# PowerStage.net
KiCad netlist of a schematic drawn in Altium Designer
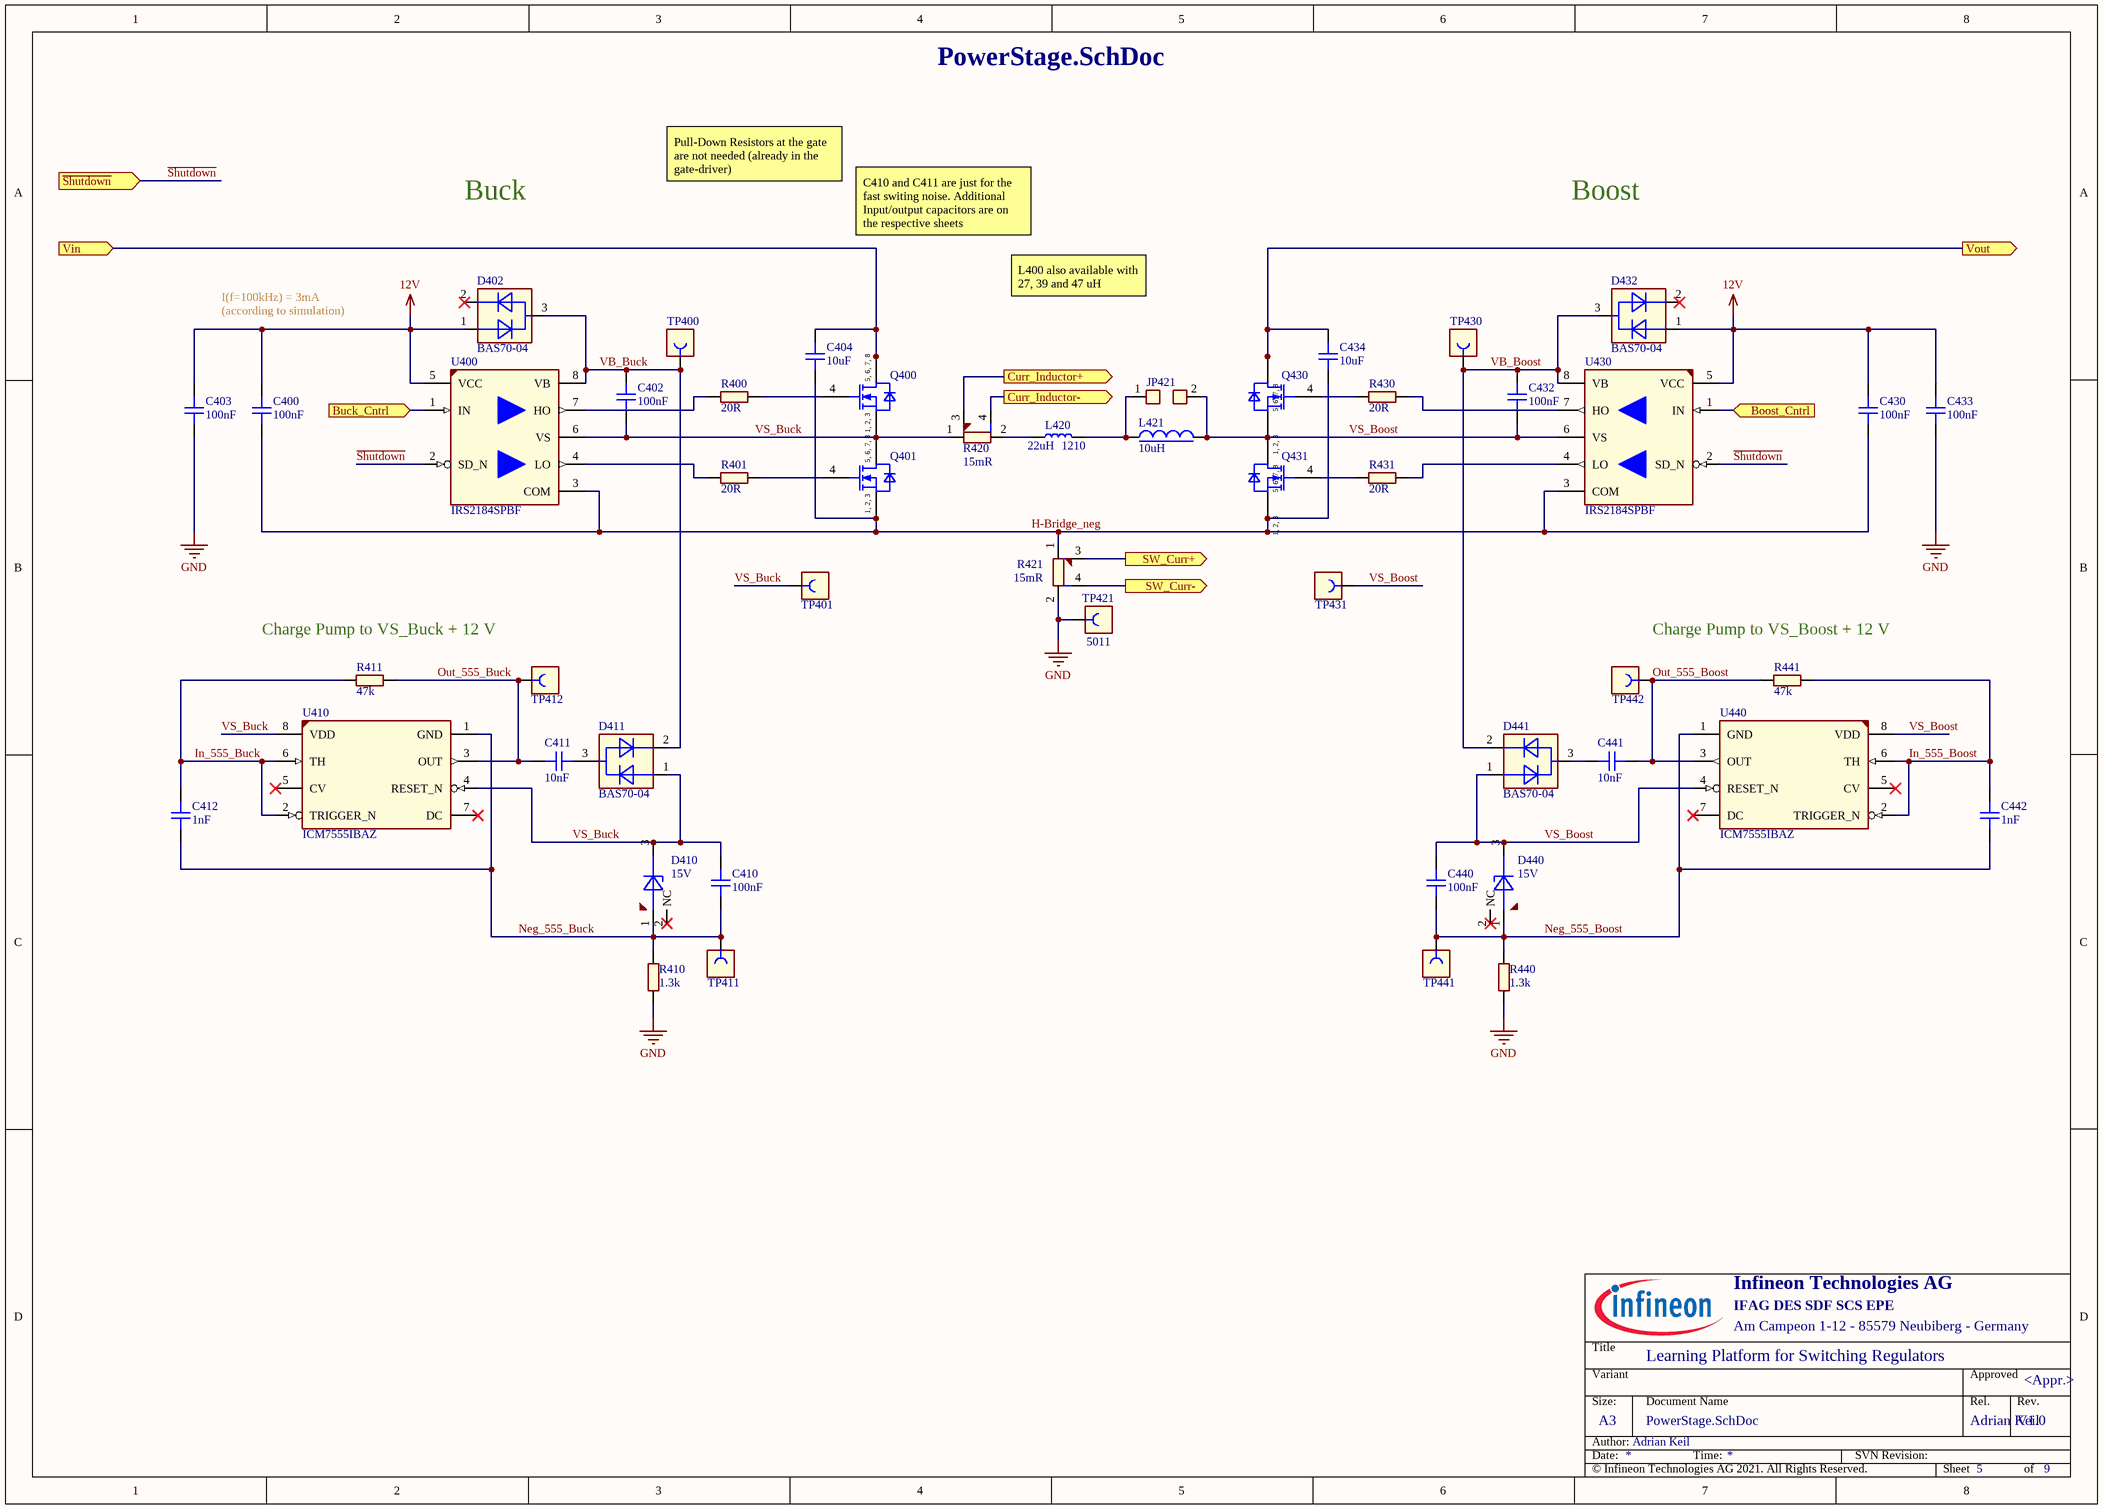
[diagram p0: PowerStage.SchDoc]

(export (version "E")
  (design (tool "Eeschema 10.0.6"))
  (components
    (comp (ref "C400")
      (value "100nF")
      (footprint "CAPC1608X90N-2")
      (description "CAP / CERA / 100nF / 50V / 10% / X7R (EIA) / -55°C to 125°C / 0603 / SMD / -")
      (fields (field (name "MANUFACTURER") "AVX"))
      (libsource (lib "PCBLibraryData") (part "CAP-SGL-STD-02P_00000001"))
    )
    (comp (ref "C402")
      (value "100nF")
      (footprint "CAPC1608X90N-2")
      (description "CAP / CERA / 100nF / 50V / 10% / X7R (EIA) / -55°C to 125°C / 0603 / SMD / -")
      (fields (field (name "MANUFACTURER") "AVX"))
      (libsource (lib "PCBLibraryData") (part "CAP-SGL-STD-02P_00000001"))
    )
    (comp (ref "C403")
      (value "100nF")
      (footprint "CAPC1608X90N-2")
      (description "CAP / CERA / 100nF / 50V / 10% / X7R (EIA) / -55°C to 125°C / 0603 / SMD / -")
      (fields (field (name "MANUFACTURER") "AVX"))
      (libsource (lib "PCBLibraryData") (part "CAP-SGL-STD-02P_00000001"))
    )
    (comp (ref "C404")
      (value "10uF")
      (footprint "CAPC3216X190N-1")
      (description "CAP / CERA / 10uF / 50V / 20% / X5R (EIA) / -55°C to 85°C / 1206 (3216) / SMD / -")
      (fields (field (name "MANUFACTURER") "Taiyo Yuden"))
      (libsource (lib "PCBLibraryData") (part "CAP-SGL-STD-02P_00000001"))
    )
    (comp (ref "C410")
      (value "100nF")
      (footprint "CAPC1608X90N-2")
      (description "CAP / CERA / 100nF / 50V / 10% / X7R (EIA) / -55°C to 125°C / 0603 / SMD / -")
      (fields (field (name "MANUFACTURER") "AVX"))
      (libsource (lib "PCBLibraryData") (part "CAP-SGL-STD-02P_00000001"))
    )
    (comp (ref "C411")
      (value "10nF")
      (footprint "CAPC1608X90N-4")
      (description "CAP / CERA / 10nF / 50V / 10% / X8R (EIA) / -55°C to 150°C / 0603(1608) / SMD / -")
      (fields
        (field (name "LEGACY PARTNUMBER") "CAP01010834")
        (field (name "MANUFACTURER") "TDK Corporation")
      )
      (libsource (lib "PCBLibraryData") (part "CAP-SGL-STD-02P_00000001"))
    )
    (comp (ref "C412")
      (value "1nF")
      (footprint "CAPC1608X87N-1")
      (description "CAP / CERA / 1nF / 50V / 10% / X7R (EIA) / -55°C to 125°C / 0603 (1608) / SMD / -")
      (fields (field (name "MANUFACTURER") "Wurth Elektronik"))
      (libsource (lib "PCBLibraryData") (part "CAP-SGL-STD-02P_00000001"))
    )
    (comp (ref "C430")
      (value "100nF")
      (footprint "CAPC1608X90N-2")
      (description "CAP / CERA / 100nF / 50V / 10% / X7R (EIA) / -55°C to 125°C / 0603 / SMD / -")
      (fields (field (name "MANUFACTURER") "AVX"))
      (libsource (lib "PCBLibraryData") (part "CAP-SGL-STD-02P_00000001"))
    )
    (comp (ref "C432")
      (value "100nF")
      (footprint "CAPC1608X90N-2")
      (description "CAP / CERA / 100nF / 50V / 10% / X7R (EIA) / -55°C to 125°C / 0603 / SMD / -")
      (fields (field (name "MANUFACTURER") "AVX"))
      (libsource (lib "PCBLibraryData") (part "CAP-SGL-STD-02P_00000001"))
    )
    (comp (ref "C433")
      (value "100nF")
      (footprint "CAPC1608X90N-2")
      (description "CAP / CERA / 100nF / 50V / 10% / X7R (EIA) / -55°C to 125°C / 0603 / SMD / -")
      (fields (field (name "MANUFACTURER") "AVX"))
      (libsource (lib "PCBLibraryData") (part "CAP-SGL-STD-02P_00000001"))
    )
    (comp (ref "C434")
      (value "10uF")
      (footprint "CAPC3216X190N-1")
      (description "CAP / CERA / 10uF / 50V / 20% / X5R (EIA) / -55°C to 85°C / 1206 (3216) / SMD / -")
      (fields (field (name "MANUFACTURER") "Taiyo Yuden"))
      (libsource (lib "PCBLibraryData") (part "CAP-SGL-STD-02P_00000001"))
    )
    (comp (ref "C440")
      (value "100nF")
      (footprint "CAPC1608X90N-2")
      (description "CAP / CERA / 100nF / 50V / 10% / X7R (EIA) / -55°C to 125°C / 0603 / SMD / -")
      (fields (field (name "MANUFACTURER") "AVX"))
      (libsource (lib "PCBLibraryData") (part "CAP-SGL-STD-02P_00000001"))
    )
    (comp (ref "C441")
      (value "10nF")
      (footprint "CAPC1608X90N-4")
      (description "CAP / CERA / 10nF / 50V / 10% / X8R (EIA) / -55°C to 150°C / 0603(1608) / SMD / -")
      (fields
        (field (name "LEGACY PARTNUMBER") "CAP01010834")
        (field (name "MANUFACTURER") "TDK Corporation")
      )
      (libsource (lib "PCBLibraryData") (part "CAP-SGL-STD-02P_00000001"))
    )
    (comp (ref "C442")
      (value "1nF")
      (footprint "CAPC1608X87N-1")
      (description "CAP / CERA / 1nF / 50V / 10% / X7R (EIA) / -55°C to 125°C / 0603 (1608) / SMD / -")
      (fields (field (name "MANUFACTURER") "Wurth Elektronik"))
      (libsource (lib "PCBLibraryData") (part "CAP-SGL-STD-02P_00000001"))
    )
    (comp (ref "D402")
      (value "BAS70-04")
      (footprint "SOT95P240X110-3N-1")
      (description "Silicon Schottky Diode")
      (fields
        (field (name "LEGACY PARTNUMBER") "IFX01400573")
        (field (name "MANUFACTURER") "Infineon Technologies")
      )
      (libsource (lib "") (part "d_dual_a1c2ac3_3p_1"))
    )
    (comp (ref "D410")
      (value "15V")
      (footprint "SOT95P237X111-3N-1")
      (fields (field (name "MANUFACTURER") "ON Semiconductor"))
      (libsource (lib "PCBLibraryData") (part "d_zener_a1c3_3p"))
    )
    (comp (ref "D411")
      (value "BAS70-04")
      (footprint "SOT95P240X110-3N-1")
      (description "Silicon Schottky Diode")
      (fields
        (field (name "LEGACY PARTNUMBER") "IFX01400573")
        (field (name "MANUFACTURER") "Infineon Technologies")
      )
      (libsource (lib "PCBLibraryData") (part "d_dual_a1c2ac3_3p"))
    )
    (comp (ref "D432")
      (value "BAS70-04")
      (footprint "SOT95P240X110-3N-1")
      (description "Silicon Schottky Diode")
      (fields
        (field (name "LEGACY PARTNUMBER") "IFX01400573")
        (field (name "MANUFACTURER") "Infineon Technologies")
      )
      (libsource (lib "PCBLibraryData") (part "d_dual_a1c2ac3_3p"))
    )
    (comp (ref "D440")
      (value "15V")
      (footprint "SOT95P237X111-3N-1")
      (fields (field (name "MANUFACTURER") "ON Semiconductor"))
      (libsource (lib "PCBLibraryData") (part "d_zener_a1c3_3p"))
    )
    (comp (ref "D441")
      (value "BAS70-04")
      (footprint "SOT95P240X110-3N-1")
      (description "Silicon Schottky Diode")
      (fields
        (field (name "LEGACY PARTNUMBER") "IFX01400573")
        (field (name "MANUFACTURER") "Infineon Technologies")
      )
      (libsource (lib "") (part "d_dual_a1c2ac3_3p_1"))
    )
    (comp (ref "JP421")
      (value "Solder Jumper 2 Pins")
      (footprint "SOLDER_BRIDGE_0.7X1.299PAD")
      (fields
        (field (name "LEGACY PARTNUMBER") "CON01500959")
        (field (name "MANUFACTURER") "Infineon Technologies")
      )
      (libsource (lib "PCBLibraryData") (part "SJP_2P"))
    )
    (comp (ref "L420")
      (value "22uH")
      (footprint "INDM120120X1000N")
      (fields (field (name "MANUFACTURER") "Wurth Elektronik") (field (name "PACKAGEREFERENCE") "1210"))
      (libsource (lib "PCBLibraryData") (part "IND-SGL-STD-02P_00000015"))
    )
    (comp (ref "L421")
      (value "10uH")
      (footprint "IND-SMD-SRP6060FA")
      (fields (field (name "MANUFACTURER") "Bourns"))
      (libsource (lib "PCBLibraryData") (part "IND-SGL-STD-COR-02P_00000016"))
    )
    (comp (ref "Q400")
      (value "igfet_n_ch_enh_dio_1s2s3s4g5d6d7d8d_8p")
      (footprint "INF-PG-TSDSON-8-FL")
      (description "OptiMOS Power - MOSFET, 60 V")
      (fields
        (field (name "LEGACY PARTNUMBER") "IFX01400359")
        (field (name "MANUFACTURER") "Infineon Technologies")
      )
      (libsource (lib "PCBLibraryData") (part "igfet_n_ch_enh_dio_1s2s3s4g5d6d7d8d_8p"))
    )
    (comp (ref "Q401")
      (value "igfet_n_ch_enh_dio_1s2s3s4g5d6d7d8d_8p")
      (footprint "INF-PG-TSDSON-8-FL")
      (description "OptiMOS Power - MOSFET, 60 V")
      (fields
        (field (name "LEGACY PARTNUMBER") "IFX01400359")
        (field (name "MANUFACTURER") "Infineon Technologies")
      )
      (libsource (lib "PCBLibraryData") (part "igfet_n_ch_enh_dio_1s2s3s4g5d6d7d8d_8p"))
    )
    (comp (ref "Q430")
      (value "igfet_n_ch_enh_dio_1s2s3s4g5d6d7d8d_8p")
      (footprint "INF-PG-TSDSON-8-FL")
      (description "OptiMOS Power - MOSFET, 60 V")
      (fields
        (field (name "LEGACY PARTNUMBER") "IFX01400359")
        (field (name "MANUFACTURER") "Infineon Technologies")
      )
      (libsource (lib "PCBLibraryData") (part "igfet_n_ch_enh_dio_1s2s3s4g5d6d7d8d_8p"))
    )
    (comp (ref "Q431")
      (value "igfet_n_ch_enh_dio_1s2s3s4g5d6d7d8d_8p")
      (footprint "INF-PG-TSDSON-8-FL")
      (description "OptiMOS Power - MOSFET, 60 V")
      (fields
        (field (name "LEGACY PARTNUMBER") "IFX01400359")
        (field (name "MANUFACTURER") "Infineon Technologies")
      )
      (libsource (lib "PCBLibraryData") (part "igfet_n_ch_enh_dio_1s2s3s4g5d6d7d8d_8p"))
    )
    (comp (ref "R400")
      (value "20R")
      (footprint "RESC1609X50N")
      (description "RES / STD / 20R / 100mW / 1% / 100ppm/K / -55°C to 155°C / 0603 / SMD / -")
      (fields (field (name "LEGACY PARTNUMBER") "RES01800947") (field (name "MANUFACTURER") "Vishay"))
      (libsource (lib "PCBLibraryData") (part "RES-SGL-STD-02P_00000006"))
    )
    (comp (ref "R401")
      (value "20R")
      (footprint "RESC1609X50N")
      (description "RES / STD / 20R / 100mW / 1% / 100ppm/K / -55°C to 155°C / 0603 / SMD / -")
      (fields (field (name "LEGACY PARTNUMBER") "RES01800947") (field (name "MANUFACTURER") "Vishay"))
      (libsource (lib "PCBLibraryData") (part "RES-SGL-STD-02P_00000006"))
    )
    (comp (ref "R410")
      (value "1.3k")
      (footprint "RESC1609X50N")
      (description "RES / STD / 1.3k / 100mW / 1% / 100ppm/K / -55°C to 155°C / 0603 / SMD / -")
      (fields (field (name "LEGACY PARTNUMBER") "RES01801155") (field (name "MANUFACTURER") "Vishay"))
      (libsource (lib "") (part "RES-SGL-STD-02P_00000006_1"))
    )
    (comp (ref "R411")
      (value "47k")
      (footprint "RESC1609X50N")
      (description "RES / STD / 47k / 100mW / 1% / 100ppm/K / -55°C to 155°C / 0603 / SMD / -")
      (fields (field (name "LEGACY PARTNUMBER") "RES01801333") (field (name "MANUFACTURER") "Vishay"))
      (libsource (lib "PCBLibraryData") (part "RES-SGL-STD-02P_00000006"))
    )
    (comp (ref "R420")
      (value "15mR")
      (footprint "RES-SMD-L4T12")
      (description "RES / STD / 15mR / 500mW / 1% / 75ppm/K / -55°C to 155°C / 1206 (3216) / SMD / -")
      (fields (field (name "MANUFACTURER") "Ohmite"))
      (libsource (lib "") (part "RES-SHT-STD-04P_00097BE5_1"))
    )
    (comp (ref "R421")
      (value "15mR")
      (footprint "RES-SMD-L4T12")
      (description "RES / STD / 15mR / 500mW / 1% / 75ppm/K / -55°C to 155°C / 1206 (3216) / SMD / -")
      (fields (field (name "MANUFACTURER") "Ohmite"))
      (libsource (lib "PCBLibraryData") (part "RES-SHT-STD-04P_00097BE5"))
    )
    (comp (ref "R430")
      (value "20R")
      (footprint "RESC1609X50N")
      (description "RES / STD / 20R / 100mW / 1% / 100ppm/K / -55°C to 155°C / 0603 / SMD / -")
      (fields (field (name "LEGACY PARTNUMBER") "RES01800947") (field (name "MANUFACTURER") "Vishay"))
      (libsource (lib "PCBLibraryData") (part "RES-SGL-STD-02P_00000006"))
    )
    (comp (ref "R431")
      (value "20R")
      (footprint "RESC1609X50N")
      (description "RES / STD / 20R / 100mW / 1% / 100ppm/K / -55°C to 155°C / 0603 / SMD / -")
      (fields (field (name "LEGACY PARTNUMBER") "RES01800947") (field (name "MANUFACTURER") "Vishay"))
      (libsource (lib "PCBLibraryData") (part "RES-SGL-STD-02P_00000006"))
    )
    (comp (ref "R440")
      (value "1.3k")
      (footprint "RESC1609X50N")
      (description "RES / STD / 1.3k / 100mW / 1% / 100ppm/K / -55°C to 155°C / 0603 / SMD / -")
      (fields (field (name "LEGACY PARTNUMBER") "RES01801155") (field (name "MANUFACTURER") "Vishay"))
      (libsource (lib "") (part "RES-SGL-STD-02P_00000006_1"))
    )
    (comp (ref "R441")
      (value "47k")
      (footprint "RESC1609X50N")
      (description "RES / STD / 47k / 100mW / 1% / 100ppm/K / -55°C to 155°C / 0603 / SMD / -")
      (fields (field (name "LEGACY PARTNUMBER") "RES01801333") (field (name "MANUFACTURER") "Vishay"))
      (libsource (lib "") (part "RES-SGL-STD-02P_00000006_1"))
    )
    (comp (ref "TP400")
      (value "S1751-46R")
      (footprint "CON-SMD-TT-S1751-46")
      (description "Test Terminal, Surface Mount (Tape and Reeled Components)")
      (fields (field (name "LEGACY PARTNUMBER") "CON01501015") (field (name "MANUFACTURER") "Harwin"))
      (libsource (lib "") (part "connector_1_f_2"))
    )
    (comp (ref "TP401")
      (value "S1751-46R")
      (footprint "CON-SMD-TT-S1751-46")
      (description "Test Terminal, Surface Mount (Tape and Reeled Components)")
      (fields (field (name "LEGACY PARTNUMBER") "CON01501015") (field (name "MANUFACTURER") "Harwin"))
      (libsource (lib "PCBLibraryData") (part "connector_1_f"))
    )
    (comp (ref "TP411")
      (value "S1751-46R")
      (footprint "CON-SMD-TT-S1751-46")
      (description "Test Terminal, Surface Mount (Tape and Reeled Components)")
      (fields (field (name "LEGACY PARTNUMBER") "CON01501015") (field (name "MANUFACTURER") "Harwin"))
      (libsource (lib "") (part "connector_1_f_3"))
    )
    (comp (ref "TP412")
      (value "S1751-46R")
      (footprint "CON-SMD-TT-S1751-46")
      (description "Test Terminal, Surface Mount (Tape and Reeled Components)")
      (fields (field (name "LEGACY PARTNUMBER") "CON01501015") (field (name "MANUFACTURER") "Harwin"))
      (libsource (lib "PCBLibraryData") (part "connector_1_f"))
    )
    (comp (ref "TP421")
      (value "5011")
      (footprint "CON-THT-TP-5011")
      (description "PC Test Point-Multipurpose THT, Black")
      (fields
        (field (name "LEGACY PARTNUMBER") "CON01500530")
        (field (name "MANUFACTURER") "Keystone Electronics Corp.")
      )
      (libsource (lib "") (part "connector_1_f_4"))
    )
    (comp (ref "TP430")
      (value "S1751-46R")
      (footprint "CON-SMD-TT-S1751-46")
      (description "Test Terminal, Surface Mount (Tape and Reeled Components)")
      (fields (field (name "LEGACY PARTNUMBER") "CON01501015") (field (name "MANUFACTURER") "Harwin"))
      (libsource (lib "") (part "connector_1_f_2"))
    )
    (comp (ref "TP431")
      (value "S1751-46R")
      (footprint "CON-SMD-TT-S1751-46")
      (description "Test Terminal, Surface Mount (Tape and Reeled Components)")
      (fields (field (name "LEGACY PARTNUMBER") "CON01501015") (field (name "MANUFACTURER") "Harwin"))
      (libsource (lib "") (part "connector_1_f_1"))
    )
    (comp (ref "TP441")
      (value "S1751-46R")
      (footprint "CON-SMD-TT-S1751-46")
      (description "Test Terminal, Surface Mount (Tape and Reeled Components)")
      (fields (field (name "LEGACY PARTNUMBER") "CON01501015") (field (name "MANUFACTURER") "Harwin"))
      (libsource (lib "") (part "connector_1_f_3"))
    )
    (comp (ref "TP442")
      (value "S1751-46R")
      (footprint "CON-SMD-TT-S1751-46")
      (description "Test Terminal, Surface Mount (Tape and Reeled Components)")
      (fields (field (name "LEGACY PARTNUMBER") "CON01501015") (field (name "MANUFACTURER") "Harwin"))
      (libsource (lib "") (part "connector_1_f_1"))
    )
    (comp (ref "U400")
      (value "IRS2184SPBF")
      (footprint "SOIC127P600X175-8N-12-V")
      (fields (field (name "MANUFACTURER") "Infineon Technologies"))
      (libsource (lib "") (part "IRS2184S_1"))
    )
    (comp (ref "U410")
      (value "ICM7555IBAZ")
      (footprint "SOIC127P600X175-8N-12")
      (description "General Purpose Timers")
      (fields (field (name "MANUFACTURER") "Renesas"))
      (libsource (lib "") (part "ICM7555_1"))
    )
    (comp (ref "U430")
      (value "IRS2184SPBF")
      (footprint "SOIC127P600X175-8N-12-V")
      (fields (field (name "MANUFACTURER") "Infineon Technologies"))
      (libsource (lib "PCBLibraryData") (part "IRS2184S"))
    )
    (comp (ref "U440")
      (value "ICM7555IBAZ")
      (footprint "SOIC127P600X175-8N-12")
      (description "General Purpose Timers")
      (fields (field (name "MANUFACTURER") "Renesas"))
      (libsource (lib "PCBLibraryData") (part "ICM7555"))
    )
  )
  (nets
    (net (code "2") (name "/Boost_Cntrl") (class "Default")
      (node (ref "U430") (pin "1") (pinfunction "IN_1") (pintype "input"))
    )
    (net (code "3") (name "/Buck_Cntrl") (class "Default")
      (node (ref "U400") (pin "1") (pinfunction "IN_1") (pintype "input"))
    )
    (net (code "4") (name "/Curr_Inductor+") (class "Default")
      (node (ref "R420") (pin "3") (pinfunction "I1_3") (pintype "passive"))
    )
    (net (code "5") (name "/Curr_Inductor-") (class "Default")
      (node (ref "R420") (pin "4") (pinfunction "I2_4") (pintype "passive"))
    )
    (net (code "6") (name "/H-Bridge_neg") (class "Default")
      (node (ref "C400") (pin "1") (pinfunction "1_1") (pintype "passive"))
      (node (ref "C404") (pin "1") (pinfunction "1_1") (pintype "passive"))
      (node (ref "C430") (pin "1") (pinfunction "1_1") (pintype "passive"))
      (node (ref "C434") (pin "1") (pinfunction "1_1") (pintype "passive"))
      (node (ref "Q401") (pin "1") (pinfunction "SOURCE_1") (pintype "passive"))
      (node (ref "Q401") (pin "2") (pinfunction "SOURCE_2") (pintype "passive"))
      (node (ref "Q401") (pin "3") (pinfunction "SOURCE_3") (pintype "passive"))
      (node (ref "Q431") (pin "1") (pinfunction "SOURCE_1") (pintype "passive"))
      (node (ref "Q431") (pin "2") (pinfunction "SOURCE_2") (pintype "passive"))
      (node (ref "Q431") (pin "3") (pinfunction "SOURCE_3") (pintype "passive"))
      (node (ref "R421") (pin "1") (pinfunction "V1_1") (pintype "passive"))
      (node (ref "U400") (pin "3") (pinfunction "COM_3") (pintype "passive"))
      (node (ref "U430") (pin "3") (pinfunction "COM_3") (pintype "passive"))
    )
    (net (code "7") (name "/In_555_Boost") (class "Default")
      (node (ref "C442") (pin "2") (pinfunction "2_2") (pintype "passive"))
      (node (ref "R441") (pin "2") (pinfunction "2_2") (pintype "passive"))
      (node (ref "U440") (pin "2") (pinfunction "TRIGGER_N_2") (pintype "input"))
      (node (ref "U440") (pin "6") (pinfunction "TH_6") (pintype "input"))
    )
    (net (code "8") (name "/In_555_Buck") (class "Default")
      (node (ref "C412") (pin "2") (pinfunction "2_2") (pintype "passive"))
      (node (ref "R411") (pin "2") (pinfunction "2_2") (pintype "passive"))
      (node (ref "U410") (pin "2") (pinfunction "TRIGGER_N_2") (pintype "input"))
      (node (ref "U410") (pin "6") (pinfunction "TH_6") (pintype "input"))
    )
    (net (code "9") (name "/Neg_555_Boost") (class "Default")
      (node (ref "C440") (pin "1") (pinfunction "1_1") (pintype "passive"))
      (node (ref "C442") (pin "1") (pinfunction "1_1") (pintype "passive"))
      (node (ref "D440") (pin "1") (pinfunction "ANODE_1") (pintype "passive"))
      (node (ref "R440") (pin "2") (pinfunction "2_2") (pintype "passive"))
      (node (ref "TP441") (pin "1") (pinfunction "1_1") (pintype "passive"))
      (node (ref "U440") (pin "1") (pinfunction "GND_1") (pintype "power_in"))
    )
    (net (code "10") (name "/Neg_555_Buck") (class "Default")
      (node (ref "C410") (pin "1") (pinfunction "1_1") (pintype "passive"))
      (node (ref "C412") (pin "1") (pinfunction "1_1") (pintype "passive"))
      (node (ref "D410") (pin "1") (pinfunction "ANODE_1") (pintype "passive"))
      (node (ref "R410") (pin "2") (pinfunction "2_2") (pintype "passive"))
      (node (ref "TP411") (pin "1") (pinfunction "1_1") (pintype "passive"))
      (node (ref "U410") (pin "1") (pinfunction "GND_1") (pintype "power_in"))
    )
    (net (code "11") (name "/Out_555_Boost") (class "Default")
      (node (ref "C441") (pin "1") (pinfunction "1_1") (pintype "passive"))
      (node (ref "R441") (pin "1") (pinfunction "1_1") (pintype "passive"))
      (node (ref "TP442") (pin "1") (pinfunction "1_1") (pintype "passive"))
      (node (ref "U440") (pin "3") (pinfunction "OUT_3") (pintype "output"))
    )
    (net (code "12") (name "/Out_555_Buck") (class "Default")
      (node (ref "C411") (pin "2") (pinfunction "2_2") (pintype "passive"))
      (node (ref "R411") (pin "1") (pinfunction "1_1") (pintype "passive"))
      (node (ref "TP412") (pin "1") (pinfunction "1_1") (pintype "passive"))
      (node (ref "U410") (pin "3") (pinfunction "OUT_3") (pintype "output"))
    )
    (net (code "13") (name "/SW_Curr+") (class "Default")
      (node (ref "R421") (pin "3") (pinfunction "I1_3") (pintype "passive"))
    )
    (net (code "14") (name "/SW_Curr-") (class "Default")
      (node (ref "R421") (pin "4") (pinfunction "I2_4") (pintype "passive"))
    )
    (net (code "15") (name "/Shutdown") (class "Default")
      (node (ref "U400") (pin "2") (pinfunction "SD_N_2") (pintype "input"))
      (node (ref "U430") (pin "2") (pinfunction "SD_N_2") (pintype "input"))
    )
    (net (code "16") (name "/VB_Boost") (class "Default")
      (node (ref "C432") (pin "2") (pinfunction "2_2") (pintype "passive"))
      (node (ref "D432") (pin "3") (pinfunction "ANODE_/_CATHODE_3") (pintype "passive"))
      (node (ref "D441") (pin "2") (pinfunction "CATHODE_2") (pintype "passive"))
      (node (ref "TP430") (pin "1") (pinfunction "1_1") (pintype "passive"))
      (node (ref "U430") (pin "8") (pinfunction "VB_8") (pintype "power_in"))
    )
    (net (code "17") (name "/VB_Buck") (class "Default")
      (node (ref "C402") (pin "2") (pinfunction "2_2") (pintype "passive"))
      (node (ref "D402") (pin "3") (pinfunction "ANODE_/_CATHODE_3") (pintype "passive"))
      (node (ref "D411") (pin "2") (pinfunction "CATHODE_2") (pintype "passive"))
      (node (ref "TP400") (pin "1") (pinfunction "1_1") (pintype "passive"))
      (node (ref "U400") (pin "8") (pinfunction "VB_8") (pintype "power_in"))
    )
    (net (code "18") (name "/VS_Boost") (class "Default")
      (node (ref "C432") (pin "1") (pinfunction "1_1") (pintype "passive"))
      (node (ref "C440") (pin "2") (pinfunction "2_2") (pintype "passive"))
      (node (ref "D440") (pin "3") (pinfunction "CATHODE_3") (pintype "passive"))
      (node (ref "D441") (pin "1") (pinfunction "ANODE_1") (pintype "passive"))
      (node (ref "JP421") (pin "2") (pinfunction "2_2") (pintype "passive"))
      (node (ref "L421") (pin "2") (pinfunction "2_2") (pintype "passive"))
      (node (ref "Q430") (pin "1") (pinfunction "SOURCE_1") (pintype "passive"))
      (node (ref "Q430") (pin "2") (pinfunction "SOURCE_2") (pintype "passive"))
      (node (ref "Q430") (pin "3") (pinfunction "SOURCE_3") (pintype "passive"))
      (node (ref "Q431") (pin "5") (pinfunction "DRAIN_5") (pintype "passive"))
      (node (ref "Q431") (pin "6") (pinfunction "DRAIN_6") (pintype "passive"))
      (node (ref "Q431") (pin "7") (pinfunction "DRAIN_7") (pintype "passive"))
      (node (ref "Q431") (pin "8") (pinfunction "DRAIN_8") (pintype "passive"))
      (node (ref "TP431") (pin "1") (pinfunction "1_1") (pintype "passive"))
      (node (ref "U430") (pin "6") (pinfunction "VS_6") (pintype "power_in"))
      (node (ref "U440") (pin "4") (pinfunction "RESET_N_4") (pintype "input"))
      (node (ref "U440") (pin "8") (pinfunction "VDD_8") (pintype "power_in"))
    )
    (net (code "19") (name "/VS_Buck") (class "Default")
      (node (ref "C402") (pin "1") (pinfunction "1_1") (pintype "passive"))
      (node (ref "C410") (pin "2") (pinfunction "2_2") (pintype "passive"))
      (node (ref "D410") (pin "3") (pinfunction "CATHODE_3") (pintype "passive"))
      (node (ref "D411") (pin "1") (pinfunction "ANODE_1") (pintype "passive"))
      (node (ref "Q400") (pin "1") (pinfunction "SOURCE_1") (pintype "passive"))
      (node (ref "Q400") (pin "2") (pinfunction "SOURCE_2") (pintype "passive"))
      (node (ref "Q400") (pin "3") (pinfunction "SOURCE_3") (pintype "passive"))
      (node (ref "Q401") (pin "5") (pinfunction "DRAIN_5") (pintype "passive"))
      (node (ref "Q401") (pin "6") (pinfunction "DRAIN_6") (pintype "passive"))
      (node (ref "Q401") (pin "7") (pinfunction "DRAIN_7") (pintype "passive"))
      (node (ref "Q401") (pin "8") (pinfunction "DRAIN_8") (pintype "passive"))
      (node (ref "R420") (pin "1") (pinfunction "V1_1") (pintype "passive"))
      (node (ref "TP401") (pin "1") (pinfunction "1_1") (pintype "passive"))
      (node (ref "U400") (pin "6") (pinfunction "VS_6") (pintype "power_in"))
      (node (ref "U410") (pin "4") (pinfunction "RESET_N_4") (pintype "input"))
      (node (ref "U410") (pin "8") (pinfunction "VDD_8") (pintype "power_in"))
    )
    (net (code "20") (name "/Vin") (class "Default")
      (node (ref "C404") (pin "2") (pinfunction "2_2") (pintype "passive"))
      (node (ref "Q400") (pin "5") (pinfunction "DRAIN_5") (pintype "passive"))
      (node (ref "Q400") (pin "6") (pinfunction "DRAIN_6") (pintype "passive"))
      (node (ref "Q400") (pin "7") (pinfunction "DRAIN_7") (pintype "passive"))
      (node (ref "Q400") (pin "8") (pinfunction "DRAIN_8") (pintype "passive"))
    )
    (net (code "21") (name "/Vout") (class "Default")
      (node (ref "C434") (pin "2") (pinfunction "2_2") (pintype "passive"))
      (node (ref "Q430") (pin "5") (pinfunction "DRAIN_5") (pintype "passive"))
      (node (ref "Q430") (pin "6") (pinfunction "DRAIN_6") (pintype "passive"))
      (node (ref "Q430") (pin "7") (pinfunction "DRAIN_7") (pintype "passive"))
      (node (ref "Q430") (pin "8") (pinfunction "DRAIN_8") (pintype "passive"))
    )
    (net (code "22") (name "12V") (class "Default")
      (node (ref "C400") (pin "2") (pinfunction "2_2") (pintype "passive"))
      (node (ref "C403") (pin "2") (pinfunction "2_2") (pintype "passive"))
      (node (ref "C430") (pin "2") (pinfunction "2_2") (pintype "passive"))
      (node (ref "C433") (pin "2") (pinfunction "2_2") (pintype "passive"))
      (node (ref "D402") (pin "1") (pinfunction "ANODE_1") (pintype "passive"))
      (node (ref "D432") (pin "1") (pinfunction "ANODE_1") (pintype "passive"))
      (node (ref "U400") (pin "5") (pinfunction "VCC_5") (pintype "power_in"))
      (node (ref "U430") (pin "5") (pinfunction "VCC_5") (pintype "power_in"))
    )
    (net (code "23") (name "GND") (class "Default")
      (node (ref "C403") (pin "1") (pinfunction "1_1") (pintype "passive"))
      (node (ref "C433") (pin "1") (pinfunction "1_1") (pintype "passive"))
      (node (ref "R410") (pin "1") (pinfunction "1_1") (pintype "passive"))
      (node (ref "R421") (pin "2") (pinfunction "V2_2") (pintype "passive"))
      (node (ref "R440") (pin "1") (pinfunction "1_1") (pintype "passive"))
      (node (ref "TP421") (pin "1") (pinfunction "1_1") (pintype "passive"))
    )
    (net (code "24") (name "Net-(D411-ANODE_{slash}_CATHODE)") (class "Default")
      (node (ref "C411") (pin "1") (pinfunction "1_1") (pintype "passive"))
      (node (ref "D411") (pin "3") (pinfunction "ANODE_/_CATHODE_3") (pintype "passive"))
    )
    (net (code "25") (name "Net-(D441-ANODE_{slash}_CATHODE)") (class "Default")
      (node (ref "C441") (pin "2") (pinfunction "2_2") (pintype "passive"))
      (node (ref "D441") (pin "3") (pinfunction "ANODE_/_CATHODE_3") (pintype "passive"))
    )
    (net (code "26") (name "Net-(JP421-Pad1)") (class "Default")
      (node (ref "JP421") (pin "1") (pinfunction "1_1") (pintype "passive"))
      (node (ref "L420") (pin "2") (pinfunction "2_2") (pintype "passive"))
      (node (ref "L421") (pin "1") (pinfunction "1_1") (pintype "passive"))
    )
    (net (code "27") (name "Net-(Q400-GATE)") (class "Default")
      (node (ref "Q400") (pin "4") (pinfunction "GATE_4") (pintype "passive"))
      (node (ref "R400") (pin "1") (pinfunction "1_1") (pintype "passive"))
    )
    (net (code "28") (name "Net-(Q401-GATE)") (class "Default")
      (node (ref "Q401") (pin "4") (pinfunction "GATE_4") (pintype "passive"))
      (node (ref "R401") (pin "1") (pinfunction "1_1") (pintype "passive"))
    )
    (net (code "29") (name "Net-(Q430-GATE)") (class "Default")
      (node (ref "Q430") (pin "4") (pinfunction "GATE_4") (pintype "passive"))
      (node (ref "R430") (pin "2") (pinfunction "2_2") (pintype "passive"))
    )
    (net (code "30") (name "Net-(Q431-GATE)") (class "Default")
      (node (ref "Q431") (pin "4") (pinfunction "GATE_4") (pintype "passive"))
      (node (ref "R431") (pin "2") (pinfunction "2_2") (pintype "passive"))
    )
    (net (code "31") (name "Net-(R420-V2)") (class "Default")
      (node (ref "L420") (pin "1") (pinfunction "1_1") (pintype "passive"))
      (node (ref "R420") (pin "2") (pinfunction "V2_2") (pintype "passive"))
    )
    (net (code "32") (name "Net-(U400-HO)") (class "Default")
      (node (ref "R400") (pin "2") (pinfunction "2_2") (pintype "passive"))
      (node (ref "U400") (pin "7") (pinfunction "HO_7") (pintype "output"))
    )
    (net (code "33") (name "Net-(U400-LO)") (class "Default")
      (node (ref "R401") (pin "2") (pinfunction "2_2") (pintype "passive"))
      (node (ref "U400") (pin "4") (pinfunction "LO_4") (pintype "output"))
    )
    (net (code "34") (name "Net-(U430-HO)") (class "Default")
      (node (ref "R430") (pin "1") (pinfunction "1_1") (pintype "passive"))
      (node (ref "U430") (pin "7") (pinfunction "HO_7") (pintype "output"))
    )
    (net (code "35") (name "Net-(U430-LO)") (class "Default")
      (node (ref "R431") (pin "1") (pinfunction "1_1") (pintype "passive"))
      (node (ref "U430") (pin "4") (pinfunction "LO_4") (pintype "output"))
    )
    (net (code "36") (name "unconnected-(D402-CATHODE-Pad2)") (class "Default")
      (node (ref "D402") (pin "2") (pinfunction "CATHODE_2") (pintype "passive+no_connect"))
    )
    (net (code "37") (name "unconnected-(D410-NC-Pad2)") (class "Default")
      (node (ref "D410") (pin "2") (pinfunction "NC_2") (pintype "passive+no_connect"))
    )
    (net (code "38") (name "unconnected-(D432-CATHODE-Pad2)") (class "Default")
      (node (ref "D432") (pin "2") (pinfunction "CATHODE_2") (pintype "passive+no_connect"))
    )
    (net (code "39") (name "unconnected-(D440-NC-Pad2)") (class "Default")
      (node (ref "D440") (pin "2") (pinfunction "NC_2") (pintype "passive+no_connect"))
    )
    (net (code "40") (name "unconnected-(U410-CV-Pad5)") (class "Default")
      (node (ref "U410") (pin "5") (pinfunction "CV_5") (pintype "power_in+no_connect"))
    )
    (net (code "41") (name "unconnected-(U410-DC-Pad7)") (class "Default")
      (node (ref "U410") (pin "7") (pinfunction "DC_7") (pintype "passive+no_connect"))
    )
    (net (code "42") (name "unconnected-(U440-CV-Pad5)") (class "Default")
      (node (ref "U440") (pin "5") (pinfunction "CV_5") (pintype "power_in+no_connect"))
    )
    (net (code "43") (name "unconnected-(U440-DC-Pad7)") (class "Default")
      (node (ref "U440") (pin "7") (pinfunction "DC_7") (pintype "passive+no_connect"))
    )
  )
)
